# untitled.net
KiCad netlist of a schematic drawn in EAGLE
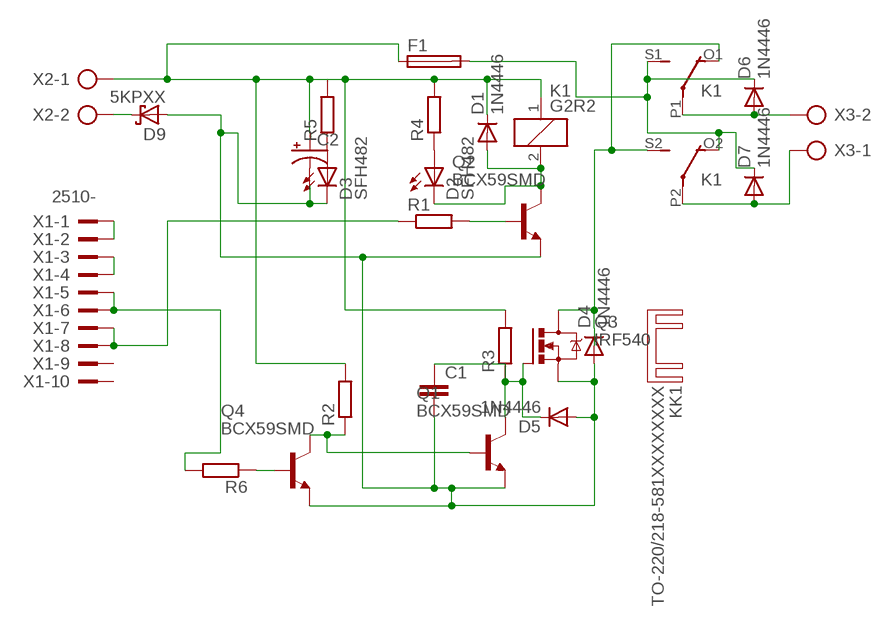
[diagram p0: schematic, sheet 1]

(export (version "E")
  (design (tool "Eeschema 10.0.6"))
  (components
    (comp (ref "C1")
      (value "C5/3")
      (footprint "eagle-import:C5B3")
      (libsource (lib "eagle-import") (part "C5/3"))
    )
    (comp (ref "C2")
      (value "CPOL-USE7.5-16")
      (footprint "eagle-import:E7,5-16")
      (libsource (lib "eagle-import") (part "CPOL-USE7.5-16"))
    )
    (comp (ref "D1")
      (value "1N4446")
      (footprint "eagle-import:DO35-10")
      (libsource (lib "eagle-import") (part "1N4446"))
    )
    (comp (ref "D2")
      (value "SFH482")
      (footprint "eagle-import:SFH482")
      (libsource (lib "eagle-import") (part "SFH482"))
    )
    (comp (ref "D3")
      (value "SFH482")
      (footprint "eagle-import:SFH482")
      (libsource (lib "eagle-import") (part "SFH482"))
    )
    (comp (ref "D4")
      (value "1N4446")
      (footprint "eagle-import:DO35-10")
      (libsource (lib "eagle-import") (part "1N4446"))
    )
    (comp (ref "D5")
      (value "1N4446")
      (footprint "eagle-import:DO35-10")
      (libsource (lib "eagle-import") (part "1N4446"))
    )
    (comp (ref "D6")
      (value "1N4446")
      (footprint "eagle-import:DO35-10")
      (libsource (lib "eagle-import") (part "1N4446"))
    )
    (comp (ref "D7")
      (value "1N4446")
      (footprint "eagle-import:DO35-10")
      (libsource (lib "eagle-import") (part "1N4446"))
    )
    (comp (ref "D9")
      (value "5KPXX")
      (footprint "eagle-import:P6T15")
      (libsource (lib "eagle-import") (part "5KPXX"))
    )
    (comp (ref "F1")
      (value "SH22,5")
      (footprint "eagle-import:SH22,5")
      (fields
        (field (name "MF") "SCHURTER")
        (field (name "MPN") "0031.8201")
        (field (name "MPN_1") "0031.8201")
        (field (name "OC_FARNELL") "1162740")
        (field (name "OC_NEWARK") "96F8317")
      )
      (libsource (lib "eagle-import") (part "SH22,5"))
    )
    (comp (ref "K1")
      (value "G2R2")
      (footprint "eagle-import:G2R2")
      (fields (field (name "MF") "OMRON COMPONENTS USA") (field (name "MPN") "G2R-2-DC6"))
      (libsource (lib "eagle-import") (part "G2R2"))
    )
    (comp (ref "KK1")
      (value "TO-220/218-581XXXXXXXX")
      (footprint "eagle-import:581XXXXXXXX")
      (libsource (lib "eagle-import") (part "TO-220/218-581XXXXXXXX"))
    )
    (comp (ref "Q1")
      (value "BCX59SMD")
      (footprint "eagle-import:TO92-EBC")
      (libsource (lib "eagle-import") (part "BCX59SMD"))
    )
    (comp (ref "Q2")
      (value "BCX59SMD")
      (footprint "eagle-import:TO92-EBC")
      (libsource (lib "eagle-import") (part "BCX59SMD"))
    )
    (comp (ref "Q3")
      (value "IRF540")
      (footprint "eagle-import:TO220BV")
      (libsource (lib "eagle-import") (part "IRF540"))
    )
    (comp (ref "Q4")
      (value "BCX59SMD")
      (footprint "eagle-import:TO92-EBC")
      (libsource (lib "eagle-import") (part "BCX59SMD"))
    )
    (comp (ref "R1")
      (value "R-EU_0207/10")
      (footprint "eagle-import:0207_10")
      (libsource (lib "eagle-import") (part "R-EU_0207/10"))
    )
    (comp (ref "R2")
      (value "R-EU_0207/10")
      (footprint "eagle-import:0207_10")
      (libsource (lib "eagle-import") (part "R-EU_0207/10"))
    )
    (comp (ref "R3")
      (value "R-EU_0207/10")
      (footprint "eagle-import:0207_10")
      (libsource (lib "eagle-import") (part "R-EU_0207/10"))
    )
    (comp (ref "R4")
      (value "R-EU_0207/10")
      (footprint "eagle-import:0207_10")
      (libsource (lib "eagle-import") (part "R-EU_0207/10"))
    )
    (comp (ref "R5")
      (value "R-EU_0207/10")
      (footprint "eagle-import:0207_10")
      (libsource (lib "eagle-import") (part "R-EU_0207/10"))
    )
    (comp (ref "R6")
      (value "R-EU_0207/10")
      (footprint "eagle-import:0207_10")
      (libsource (lib "eagle-import") (part "R-EU_0207/10"))
    )
    (comp (ref "X1")
      (value "2510-")
      (footprint "eagle-import:PAK100_2500-10")
      (fields (field (name "MF") "3M") (field (name "MPN") "2510-6002UB"))
      (libsource (lib "eagle-import") (part "2510-"))
    )
    (comp (ref "X2")
      (value "AK300/2")
      (footprint "eagle-import:AK300_2")
      (libsource (lib "eagle-import") (part "AK300/2"))
    )
    (comp (ref "X3")
      (value "AK300/2")
      (footprint "eagle-import:AK300_2")
      (libsource (lib "eagle-import") (part "AK300/2"))
    )
  )
  (nets
    (net (code "1") (name "Net-(C1-Pad1)") (class "Default")
      (node (ref "C1") (pin "1") (pinfunction "1_1") (pintype "passive"))
      (node (ref "D5") (pin "C") (pinfunction "C_C") (pintype "passive"))
      (node (ref "Q1") (pin "C") (pinfunction "C_C") (pintype "passive"))
      (node (ref "Q3") (pin "G") (pinfunction "G_G") (pintype "passive"))
      (node (ref "R3") (pin "1") (pinfunction "1_1") (pintype "passive"))
    )
    (net (code "2") (name "Net-(D2-C)") (class "Default")
      (node (ref "D1") (pin "A") (pinfunction "A_A") (pintype "passive"))
      (node (ref "D2") (pin "K") (pinfunction "C_K") (pintype "passive"))
      (node (ref "K1") (pin "2") (pinfunction "2_2") (pintype "passive"))
      (node (ref "Q2") (pin "C") (pinfunction "C_C") (pintype "passive"))
    )
    (net (code "3") (name "Net-(D2-PadA)") (class "Default")
      (node (ref "D2") (pin "A") (pinfunction "A_A") (pintype "passive"))
      (node (ref "R4") (pin "1") (pinfunction "1_1") (pintype "passive"))
    )
    (net (code "4") (name "Net-(D3-C)") (class "Default")
      (node (ref "C1") (pin "2") (pinfunction "2_2") (pintype "passive"))
      (node (ref "C2") (pin "-") (pinfunction "-_-") (pintype "passive"))
      (node (ref "D3") (pin "K") (pinfunction "C_K") (pintype "passive"))
      (node (ref "D4") (pin "A") (pinfunction "A_A") (pintype "passive"))
      (node (ref "D5") (pin "A") (pinfunction "A_A") (pintype "passive"))
      (node (ref "D9") (pin "A") (pinfunction "A_A") (pintype "passive"))
      (node (ref "Q1") (pin "E") (pinfunction "E_E") (pintype "passive"))
      (node (ref "Q2") (pin "E") (pinfunction "E_E") (pintype "passive"))
      (node (ref "Q3") (pin "S") (pinfunction "S_S") (pintype "passive"))
      (node (ref "Q4") (pin "E") (pinfunction "E_E") (pintype "passive"))
    )
    (net (code "5") (name "Net-(D3-PadA)") (class "Default")
      (node (ref "D3") (pin "A") (pinfunction "A_A") (pintype "passive"))
      (node (ref "R5") (pin "1") (pinfunction "1_1") (pintype "passive"))
    )
    (net (code "6") (name "Net-(K1B-O)") (class "Default")
      (node (ref "D4") (pin "C") (pinfunction "C_C") (pintype "passive"))
      (node (ref "K1") (pin "O1") (pinfunction "O_O1") (pintype "passive"))
      (node (ref "K1") (pin "S2") (pinfunction "S_S2") (pintype "passive"))
      (node (ref "Q3") (pin "D") (pinfunction "D_D") (pintype "passive"))
    )
    (net (code "7") (name "Net-(K1B-P)") (class "Default")
      (node (ref "D6") (pin "A") (pinfunction "A_A") (pintype "passive"))
      (node (ref "K1") (pin "P1") (pinfunction "P_P1") (pintype "passive"))
      (node (ref "X3") (pin "2") (pinfunction "KL_2") (pintype "passive"))
    )
    (net (code "8") (name "Net-(K1B-S)") (class "Default")
      (node (ref "D6") (pin "C") (pinfunction "C_C") (pintype "passive"))
      (node (ref "D7") (pin "C") (pinfunction "C_C") (pintype "passive"))
      (node (ref "F1") (pin "2") (pinfunction "2_2") (pintype "passive"))
      (node (ref "K1") (pin "O2") (pinfunction "O_O2") (pintype "passive"))
      (node (ref "K1") (pin "S1") (pinfunction "S_S1") (pintype "passive"))
    )
    (net (code "9") (name "Net-(K1C-P)") (class "Default")
      (node (ref "D7") (pin "A") (pinfunction "A_A") (pintype "passive"))
      (node (ref "K1") (pin "P2") (pinfunction "P_P2") (pintype "passive"))
      (node (ref "X3") (pin "1") (pinfunction "KL_1") (pintype "passive"))
    )
    (net (code "10") (name "Net-(Q1-PadB)") (class "Default")
      (node (ref "Q1") (pin "B") (pinfunction "B_B") (pintype "passive"))
      (node (ref "Q4") (pin "C") (pinfunction "C_C") (pintype "passive"))
      (node (ref "R2") (pin "1") (pinfunction "1_1") (pintype "passive"))
    )
    (net (code "11") (name "Net-(Q2-PadB)") (class "Default")
      (node (ref "Q2") (pin "B") (pinfunction "B_B") (pintype "passive"))
      (node (ref "R1") (pin "2") (pinfunction "2_2") (pintype "passive"))
    )
    (net (code "12") (name "Net-(Q4-PadB)") (class "Default")
      (node (ref "Q4") (pin "B") (pinfunction "B_B") (pintype "passive"))
      (node (ref "R6") (pin "1") (pinfunction "1_1") (pintype "passive"))
    )
    (net (code "13") (name "Net-(X1A-KL)") (class "Default")
      (node (ref "X1") (pin "1") (pinfunction "KL_1") (pintype "passive"))
      (node (ref "X1") (pin "2") (pinfunction "KL_2") (pintype "passive"))
    )
    (net (code "14") (name "Net-(X1D-KL)") (class "Default")
      (node (ref "X1") (pin "3") (pinfunction "KL_3") (pintype "passive"))
      (node (ref "X1") (pin "4") (pinfunction "KL_4") (pintype "passive"))
    )
    (net (code "15") (name "Net-(X1F-KL)") (class "Default")
      (node (ref "R6") (pin "2") (pinfunction "2_2") (pintype "passive"))
      (node (ref "X1") (pin "5") (pinfunction "KL_5") (pintype "passive"))
      (node (ref "X1") (pin "6") (pinfunction "KL_6") (pintype "passive"))
    )
    (net (code "16") (name "Net-(X1H-KL)") (class "Default")
      (node (ref "R1") (pin "1") (pinfunction "1_1") (pintype "passive"))
      (node (ref "X1") (pin "7") (pinfunction "KL_7") (pintype "passive"))
      (node (ref "X1") (pin "8") (pinfunction "KL_8") (pintype "passive"))
    )
    (net (code "17") (name "Net-(X2A-KL)") (class "Default")
      (node (ref "C2") (pin "+") (pinfunction "+_+") (pintype "passive"))
      (node (ref "D1") (pin "C") (pinfunction "C_C") (pintype "passive"))
      (node (ref "F1") (pin "1") (pinfunction "1_1") (pintype "passive"))
      (node (ref "K1") (pin "1") (pinfunction "1_1") (pintype "passive"))
      (node (ref "R2") (pin "2") (pinfunction "2_2") (pintype "passive"))
      (node (ref "R3") (pin "2") (pinfunction "2_2") (pintype "passive"))
      (node (ref "R4") (pin "2") (pinfunction "2_2") (pintype "passive"))
      (node (ref "R5") (pin "2") (pinfunction "2_2") (pintype "passive"))
      (node (ref "X2") (pin "1") (pinfunction "KL_1") (pintype "passive"))
    )
    (net (code "18") (name "Net-(X2B-KL)") (class "Default")
      (node (ref "D9") (pin "C") (pinfunction "C_C") (pintype "passive"))
      (node (ref "X2") (pin "2") (pinfunction "KL_2") (pintype "passive"))
    )
    (net (code "19") (name "unconnected-(X1B-KL-Pad10)") (class "Default")
      (node (ref "X1") (pin "10") (pinfunction "KL_10") (pintype "passive"))
    )
    (net (code "20") (name "unconnected-(X1J-KL-Pad9)") (class "Default")
      (node (ref "X1") (pin "9") (pinfunction "KL_9") (pintype "passive"))
    )
  )
)
